# 04__Power_Sheet.net
KiCad netlist of a schematic drawn in Altium Designer
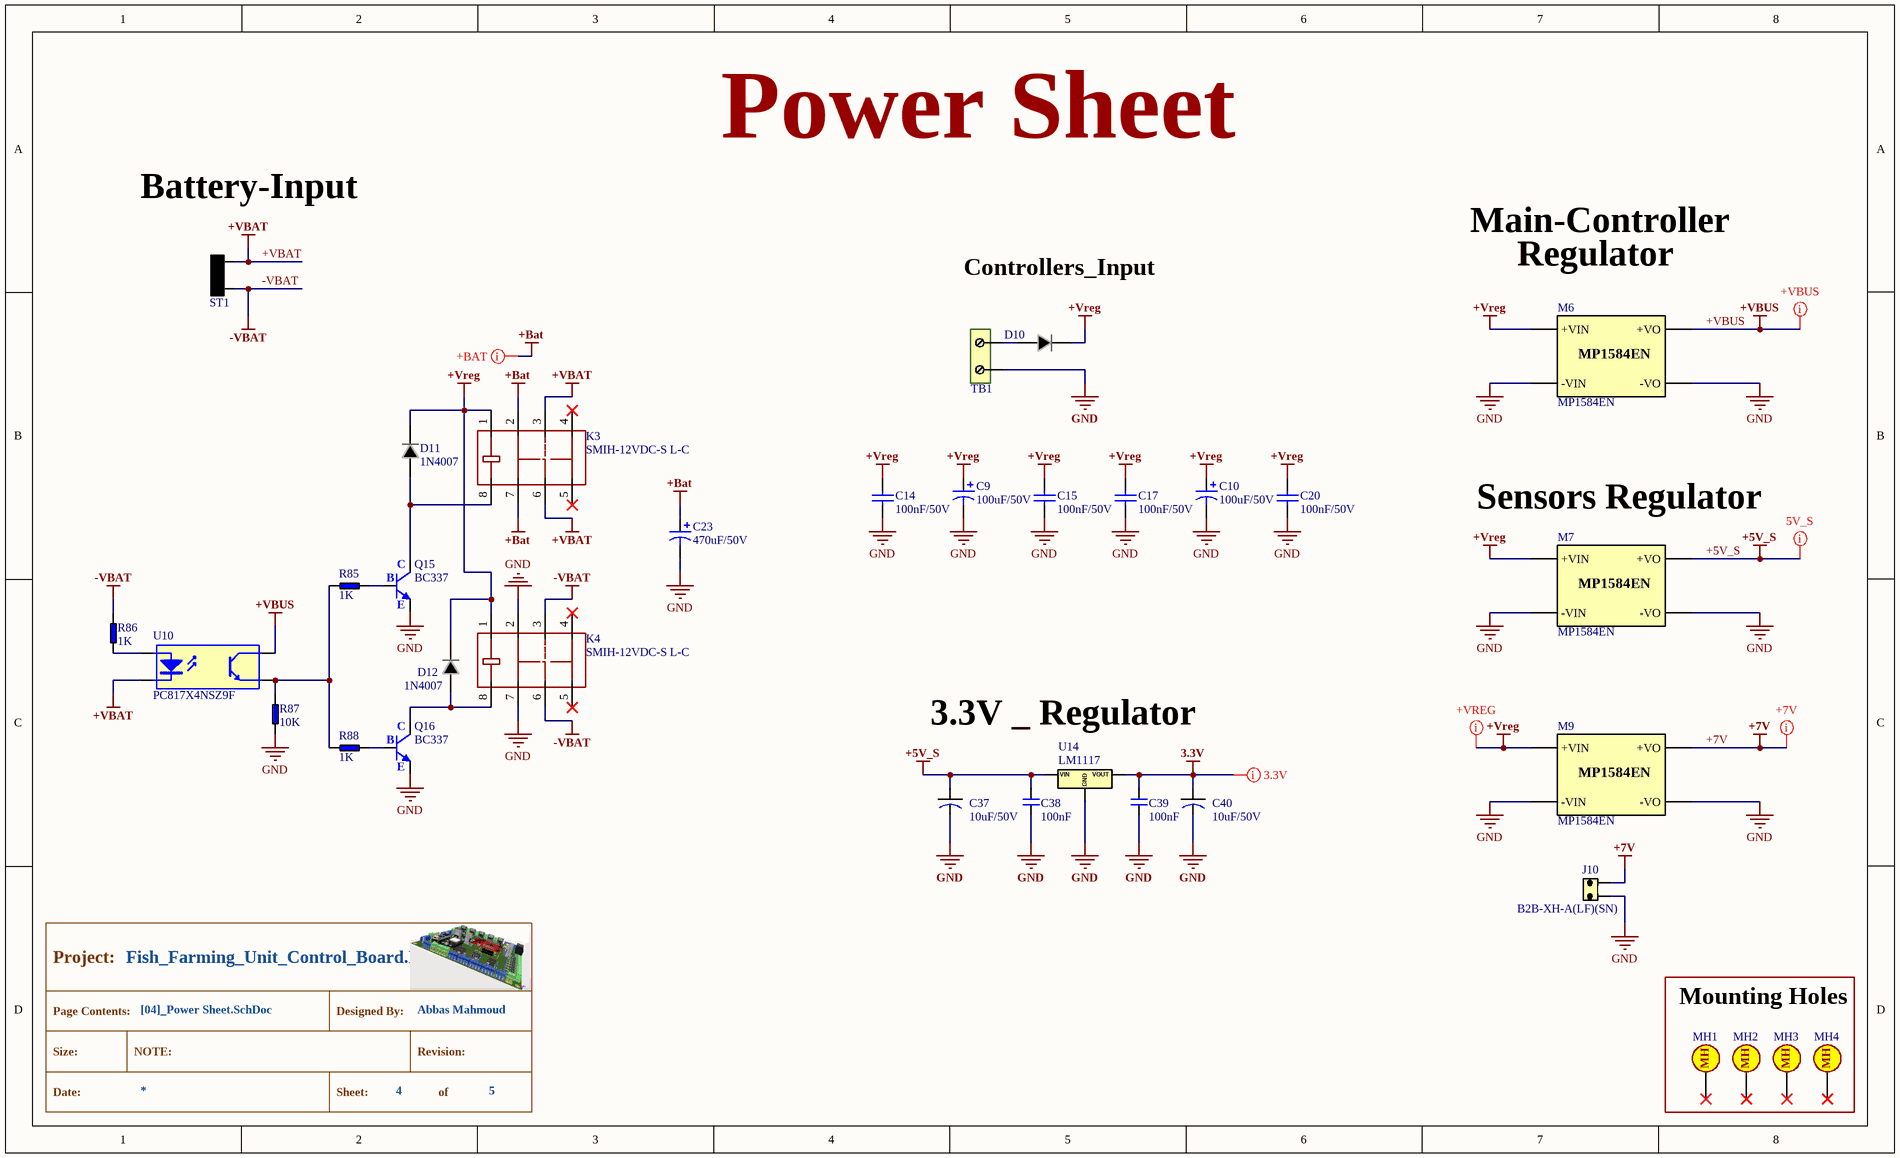
[diagram p0: [04]_Power Sheet.SchDoc]

(export (version "E")
  (design (tool "Eeschema 10.0.6"))
  (components
    (comp (ref "C9")
      (value "100uF/50V")
      (footprint "ECAP - THT - 8X12X3.5MM")
      (description "100uF ±20% 50V 8x12 1000Hrs @ 105℃ Radial,8x12mm Aluminum Electrolytic Capacitors - Leaded RoHS")
      (libsource (lib "Altium_Abbas_V3") (part "ECAP - 100uF - 50V"))
    )
    (comp (ref "C10")
      (value "100uF/50V")
      (footprint "ECAP - THT - 8X12X3.5MM")
      (description "100uF ±20% 50V 8x12 1000Hrs @ 105℃ Radial,8x12mm Aluminum Electrolytic Capacitors - Leaded RoHS")
      (libsource (lib "Altium_Abbas_V3") (part "ECAP - 100uF - 50V"))
    )
    (comp (ref "C14")
      (value "100nF/50V")
      (footprint "CCAP - PACKAGE - THT ,P = 2.54 MM")
      (description "100nF -20%~+80% 50V Through Hole,P=2.54mm Ceramic Disc Capacitors RoHS")
      (libsource (lib "Altium_Abbas_V3") (part "CCAP - 100nF - 50V - THT - P = 2.54"))
    )
    (comp (ref "C15")
      (value "100nF/50V")
      (footprint "CCAP - PACKAGE - THT ,P = 2.54 MM")
      (description "100nF -20%~+80% 50V Through Hole,P=2.54mm Ceramic Disc Capacitors RoHS")
      (libsource (lib "Altium_Abbas_V3") (part "CCAP - 100nF - 50V - THT - P = 2.54"))
    )
    (comp (ref "C17")
      (value "100nF/50V")
      (footprint "CCAP - PACKAGE - THT ,P = 2.54 MM")
      (description "100nF -20%~+80% 50V Through Hole,P=2.54mm Ceramic Disc Capacitors RoHS")
      (libsource (lib "Altium_Abbas_V3") (part "CCAP - 100nF - 50V - THT - P = 2.54"))
    )
    (comp (ref "C20")
      (value "100nF/50V")
      (footprint "CCAP - PACKAGE - THT ,P = 2.54 MM")
      (description "100nF -20%~+80% 50V Through Hole,P=2.54mm Ceramic Disc Capacitors RoHS")
      (libsource (lib "Altium_Abbas_V3") (part "CCAP - 100nF - 50V - THT - P = 2.54"))
    )
    (comp (ref "C23")
      (value "470uF/50V")
      (footprint "ECAP - THT - 10X20X5MM")
      (description "470uF ±20% 50V 10x20 1000Hrs @ 105℃ Radial,10x20mm Aluminum Electrolytic Capacitors - Leaded RoHS")
      (libsource (lib "Altium_Abbas_V3") (part "ECAP - 470uF - 50V"))
    )
    (comp (ref "C37")
      (value "10uF/50V")
      (footprint "ECAP 5X11X2MM")
      (description "10uF ±20% 50V 5x11 1000Hrs @ 105℃ Radial,5x11mm Aluminum Electrolytic Capacitors - Leaded RoHS")
      (libsource (lib "Altium_Abbas") (part "ECAP-10uF-50V"))
    )
    (comp (ref "C38")
      (value "100nF")
      (footprint "CCAP 0.1 N Y")
      (libsource (lib "Altium_Abbas") (part "Ceramic_CAP_100nF"))
    )
    (comp (ref "C39")
      (value "100nF")
      (footprint "CCAP 0.1 N Y")
      (libsource (lib "Altium_Abbas") (part "Ceramic_CAP_100nF"))
    )
    (comp (ref "C40")
      (value "10uF/50V")
      (footprint "ECAP 5X11X2MM")
      (description "10uF ±20% 50V 5x11 1000Hrs @ 105℃ Radial,5x11mm Aluminum Electrolytic Capacitors - Leaded RoHS")
      (libsource (lib "Altium_Abbas") (part "ECAP-10uF-50V"))
    )
    (comp (ref "D10")
      (value "1N4007")
      (footprint "DIODE - THT - 10.16P - PACKAGE - DO-41")
      (description "1kV 1A 1V @ 1A DO-41 Diodes - General Purpose RoHS")
      (libsource (lib "Altium_Abbas_V3") (part "Diode - 1N4007 - THT"))
    )
    (comp (ref "D11")
      (value "1N4007")
      (footprint "DIODE - THT - 7.62P - PACKAGE - DO-41")
      (description "1kV 1A 1V @ 1A DO-41 Diodes - General Purpose RoHS")
      (libsource (lib "Altium_Abbas_V3") (part "Diode - 1N4007 - THT"))
    )
    (comp (ref "D12")
      (value "1N4007")
      (footprint "DIODE - THT - 7.62P - PACKAGE - DO-41")
      (description "1kV 1A 1V @ 1A DO-41 Diodes - General Purpose RoHS")
      (libsource (lib "Altium_Abbas_V3") (part "Diode - 1N4007 - THT"))
    )
    (comp (ref "J10")
      (value "B2B-XH-A(LF)(SN)")
      (footprint "XH - 2P - Vertical - Package - THT - P = 2.54")
      (fields (field (name "MANUFACTURER") "JST Sales America"))
      (libsource (lib "Altium_Abbas_V3") (part "XH - Male Header - 2P - THT - Vertical"))
    )
    (comp (ref "K3")
      (value "SMIH-12VDC-S L-C")
      (footprint "RELAY-TH_SMIH-12VDC-SL-C")
      (description "General Purpose Non Latching 12VDC SPDT 16A Through Hole Relays RoHS")
      (libsource (lib "Altium_Abbas_V3") (part "Relay_12V_16A"))
    )
    (comp (ref "K4")
      (value "SMIH-12VDC-S L-C")
      (footprint "RELAY-TH_SMIH-12VDC-SL-C")
      (description "General Purpose Non Latching 12VDC SPDT 16A Through Hole Relays RoHS")
      (libsource (lib "Altium_Abbas_V3") (part "Relay_12V_16A"))
    )
    (comp (ref "M6")
      (value "MP1584EN")
      (footprint "DC TO D CCONVERTER - MP1584")
      (description "DC-DC 4.5-28V to 0.8-20V Output 3A MP1584EN Step Down Buck Converter")
      (libsource (lib "Altium_Modules") (part "DC TO DC CONVERTER - MP1584EN"))
    )
    (comp (ref "M7")
      (value "MP1584EN")
      (footprint "DC TO D CCONVERTER - MP1584")
      (description "DC-DC 4.5-28V to 0.8-20V Output 3A MP1584EN Step Down Buck Converter")
      (libsource (lib "Altium_Modules") (part "DC TO DC CONVERTER - MP1584EN"))
    )
    (comp (ref "M9")
      (value "MP1584EN")
      (footprint "DC TO D CCONVERTER - MP1584")
      (description "DC-DC 4.5-28V to 0.8-20V Output 3A MP1584EN Step Down Buck Converter")
      (libsource (lib "Altium_Modules") (part "DC TO DC CONVERTER - MP1584EN"))
    )
    (comp (ref "MH1")
      (value "MOUNTING HOLE")
      (footprint "MH-3.2X8mm_Round")
      (description "Mounting Hole")
      (libsource (lib "Altium_Abbas") (part "MH"))
    )
    (comp (ref "MH2")
      (value "MOUNTING HOLE")
      (footprint "MH-3.2X8mm_Round")
      (description "Mounting Hole")
      (libsource (lib "Altium_Abbas") (part "MH"))
    )
    (comp (ref "MH3")
      (value "MOUNTING HOLE")
      (footprint "MH-3.2X8mm_Round")
      (description "Mounting Hole")
      (libsource (lib "Altium_Abbas") (part "MH"))
    )
    (comp (ref "MH4")
      (value "MOUNTING HOLE")
      (footprint "MH-3.2X8mm_Round")
      (description "Mounting Hole")
      (libsource (lib "Altium_Abbas") (part "MH"))
    )
    (comp (ref "Q15")
      (value "BC337")
      (footprint "Transistor - THT - PACKAGE - TO-92 / TO-92-3")
      (description "NPN 800mA 45V 625mW TO-92(TO-92-3) Transistors (NPN/PNP) RoHS")
      (libsource (lib "Altium_Abbas_V3") (part "NPN - BC337"))
    )
    (comp (ref "Q16")
      (value "BC337")
      (footprint "Transistor - THT - PACKAGE - TO-92 / TO-92-3")
      (description "NPN 800mA 45V 625mW TO-92(TO-92-3) Transistors (NPN/PNP) RoHS")
      (libsource (lib "Altium_Abbas_V3") (part "NPN - BC337"))
    )
    (comp (ref "R85")
      (value "1K")
      (footprint "R - THT - P5.0 - 1/4W")
      (description "1K ±1% 1/4W ±100ppm/℃ Axial Metal Film Resistor_ Throuh Hole Technology RoHS")
      (libsource (lib "Altium_Abbas_V3") (part "R1K - THT"))
    )
    (comp (ref "R86")
      (value "1K")
      (footprint "R - THT - P5.0 - 1/4W")
      (description "1K ±1% 1/4W ±100ppm/℃ Axial Metal Film Resistor_ Throuh Hole Technology RoHS")
      (libsource (lib "Altium_Abbas_V3") (part "R1K - THT"))
    )
    (comp (ref "R87")
      (value "10K")
      (footprint "R - THT - P5.0 - 1/4W")
      (description "10K ±1% 1/4W ±100ppm/℃ Axial Metal Film Resistor_ Throuh Hole Technology RoHS")
      (libsource (lib "Altium_Abbas_V3") (part "R10K - THT"))
    )
    (comp (ref "R88")
      (value "1K")
      (footprint "R - THT - P5.0 - 1/4W")
      (description "1K ±1% 1/4W ±100ppm/℃ Axial Metal Film Resistor_ Throuh Hole Technology RoHS")
      (libsource (lib "Altium_Abbas_V3") (part "R1K - THT"))
    )
    (comp (ref "ST1")
      (value "SCREW TERMINAL")
      (footprint "SCREW TERMINAL")
      (description "Barrier Terminal Block 2 Pin with cover 300V/25A")
      (libsource (lib "Altium_Abbas") (part "SCREW TERMINAL"))
    )
    (comp (ref "TB1")
      (value "2 Pins Pluggable")
      (footprint "TERMINAL BLOCK - 2 PINS - PACKAGE - PLUGGABLE - THT - P = 5.08MM - Horizontal _ Plug+Receptable")
      (libsource (lib "Altium_Abbas_V3") (part "Terminal Block - 2 Pins - Pluggable"))
    )
    (comp (ref "U10")
      (value "PC817X4NSZ9F")
      (footprint "ICB - DIP-4")
      (description "Optoisolator Transistor Output 5000Vrms 1 Channel 4-DIP")
      (fields (field (name "MANUFACTURER") "Sharp Microelectronics"))
      (libsource (lib "Altium_Abbas_V3") (part "IC - PC817X4NSZ9F"))
    )
    (comp (ref "U14")
      (value "LM1117")
      (footprint "V-REG/Heatsink - TO - 220")
      (description "IC LM1117-3.3V")
      (libsource (lib "Altium_Abbas") (part "LM117"))
    )
  )
  (nets
    (net (code "1") (name "+5V_S") (class "Default")
      (node (ref "C37") (pin "A") (pintype "passive"))
      (node (ref "C38") (pin "1") (pintype "passive"))
      (node (ref "M7") (pin "+VO") (pinfunction "+VO_+VO") (pintype "power_in"))
      (node (ref "U14") (pin "3") (pinfunction "VIN_3") (pintype "passive"))
    )
    (net (code "2") (name "+7V") (class "Default")
      (node (ref "J10") (pin "2") (pinfunction "2_2") (pintype "passive"))
      (node (ref "M9") (pin "+VO") (pinfunction "+VO_+VO") (pintype "power_in"))
    )
    (net (code "3") (name "+Bat") (class "Default")
      (node (ref "C23") (pin "A") (pinfunction "A_A") (pintype "passive"))
      (node (ref "K3") (pin "2") (pinfunction "2_2") (pintype "passive"))
      (node (ref "K3") (pin "7") (pinfunction "7_7") (pintype "passive"))
    )
    (net (code "4") (name "+VBAT") (class "Default")
      (node (ref "K3") (pin "3") (pinfunction "3_3") (pintype "passive"))
      (node (ref "K3") (pin "6") (pinfunction "6_6") (pintype "passive"))
      (node (ref "ST1") (pin "1") (pinfunction "AC_1") (pintype "passive"))
      (node (ref "U10") (pin "2") (pinfunction "K_2") (pintype "passive"))
    )
    (net (code "5") (name "+VBUS") (class "Default")
      (node (ref "M6") (pin "+VO") (pinfunction "+VO_+VO") (pintype "power_in"))
      (node (ref "U10") (pin "4") (pinfunction "C_4") (pintype "passive"))
    )
    (net (code "6") (name "+Vreg") (class "Default")
      (node (ref "C10") (pin "A") (pinfunction "A_A") (pintype "passive"))
      (node (ref "C14") (pin "1") (pinfunction "1_1") (pintype "passive"))
      (node (ref "C15") (pin "1") (pinfunction "1_1") (pintype "passive"))
      (node (ref "C17") (pin "1") (pinfunction "1_1") (pintype "passive"))
      (node (ref "C20") (pin "1") (pinfunction "1_1") (pintype "passive"))
      (node (ref "C9") (pin "A") (pinfunction "A_A") (pintype "passive"))
      (node (ref "D10") (pin "K") (pinfunction "K_K") (pintype "passive"))
      (node (ref "D11") (pin "K") (pinfunction "K_K") (pintype "passive"))
      (node (ref "D12") (pin "K") (pinfunction "K_K") (pintype "passive"))
      (node (ref "K3") (pin "1") (pinfunction "1_1") (pintype "passive"))
      (node (ref "K4") (pin "1") (pinfunction "1_1") (pintype "passive"))
      (node (ref "M6") (pin "+VIN") (pinfunction "+VIN_+VIN") (pintype "power_in"))
      (node (ref "M7") (pin "+VIN") (pinfunction "+VIN_+VIN") (pintype "power_in"))
      (node (ref "M9") (pin "+VIN") (pinfunction "+VIN_+VIN") (pintype "power_in"))
    )
    (net (code "7") (name "-VBAT") (class "Default")
      (node (ref "K4") (pin "3") (pinfunction "3_3") (pintype "passive"))
      (node (ref "K4") (pin "6") (pinfunction "6_6") (pintype "passive"))
      (node (ref "R86") (pin "2") (pinfunction "6_2") (pintype "passive"))
      (node (ref "ST1") (pin "2") (pinfunction "AC_2") (pintype "passive"))
    )
    (net (code "8") (name "3.3V") (class "Default")
      (node (ref "C39") (pin "1") (pintype "passive"))
      (node (ref "C40") (pin "A") (pintype "passive"))
      (node (ref "U14") (pin "2") (pinfunction "VOUT_2") (pintype "passive"))
    )
    (net (code "9") (name "GND") (class "Default")
      (node (ref "C10") (pin "K") (pinfunction "K_K") (pintype "passive"))
      (node (ref "C14") (pin "2") (pinfunction "2_2") (pintype "passive"))
      (node (ref "C15") (pin "2") (pinfunction "2_2") (pintype "passive"))
      (node (ref "C17") (pin "2") (pinfunction "2_2") (pintype "passive"))
      (node (ref "C20") (pin "2") (pinfunction "2_2") (pintype "passive"))
      (node (ref "C23") (pin "K") (pinfunction "K_K") (pintype "passive"))
      (node (ref "C37") (pin "K") (pintype "passive"))
      (node (ref "C38") (pin "2") (pintype "passive"))
      (node (ref "C39") (pin "2") (pintype "passive"))
      (node (ref "C40") (pin "K") (pintype "passive"))
      (node (ref "C9") (pin "K") (pinfunction "K_K") (pintype "passive"))
      (node (ref "J10") (pin "1") (pinfunction "1_1") (pintype "passive"))
      (node (ref "K4") (pin "2") (pinfunction "2_2") (pintype "passive"))
      (node (ref "K4") (pin "7") (pinfunction "7_7") (pintype "passive"))
      (node (ref "M6") (pin "-VIN") (pinfunction "-VIN_-VIN") (pintype "power_in"))
      (node (ref "M6") (pin "-VO") (pinfunction "-VO_-VO") (pintype "power_in"))
      (node (ref "M7") (pin "-VIN") (pinfunction "-VIN_-VIN") (pintype "power_in"))
      (node (ref "M7") (pin "-VO") (pinfunction "-VO_-VO") (pintype "power_in"))
      (node (ref "M9") (pin "-VIN") (pinfunction "-VIN_-VIN") (pintype "power_in"))
      (node (ref "M9") (pin "-VO") (pinfunction "-VO_-VO") (pintype "power_in"))
      (node (ref "Q15") (pin "1") (pinfunction "E_1") (pintype "passive"))
      (node (ref "Q16") (pin "1") (pinfunction "E_1") (pintype "passive"))
      (node (ref "R87") (pin "1") (pinfunction "5_1") (pintype "passive"))
      (node (ref "TB1") (pin "2") (pinfunction "2_2") (pintype "passive"))
      (node (ref "U14") (pin "1") (pinfunction "GND_1") (pintype "passive"))
    )
    (net (code "10") (name "Net-(D10-PadA)") (class "Default")
      (node (ref "D10") (pin "A") (pinfunction "A_A") (pintype "passive"))
      (node (ref "TB1") (pin "1") (pinfunction "1_1") (pintype "passive"))
    )
    (net (code "11") (name "Net-(Q15-B)") (class "Default")
      (node (ref "Q15") (pin "2") (pinfunction "B_2") (pintype "passive"))
      (node (ref "R85") (pin "2") (pinfunction "6_2") (pintype "passive"))
    )
    (net (code "12") (name "Net-(Q15-C)") (class "Default")
      (node (ref "D11") (pin "A") (pinfunction "A_A") (pintype "passive"))
      (node (ref "K3") (pin "8") (pinfunction "8_8") (pintype "passive"))
      (node (ref "Q15") (pin "3") (pinfunction "C_3") (pintype "passive"))
    )
    (net (code "13") (name "Net-(Q16-B)") (class "Default")
      (node (ref "Q16") (pin "2") (pinfunction "B_2") (pintype "passive"))
      (node (ref "R88") (pin "2") (pinfunction "6_2") (pintype "passive"))
    )
    (net (code "14") (name "Net-(Q16-C)") (class "Default")
      (node (ref "D12") (pin "A") (pinfunction "A_A") (pintype "passive"))
      (node (ref "K4") (pin "8") (pinfunction "8_8") (pintype "passive"))
      (node (ref "Q16") (pin "3") (pinfunction "C_3") (pintype "passive"))
    )
    (net (code "15") (name "Net-(R85-5)") (class "Default")
      (node (ref "R85") (pin "1") (pinfunction "5_1") (pintype "passive"))
      (node (ref "R87") (pin "2") (pinfunction "6_2") (pintype "passive"))
      (node (ref "R88") (pin "1") (pinfunction "5_1") (pintype "passive"))
      (node (ref "U10") (pin "3") (pinfunction "E_3") (pintype "passive"))
    )
    (net (code "16") (name "Net-(R86-5)") (class "Default")
      (node (ref "R86") (pin "1") (pinfunction "5_1") (pintype "passive"))
      (node (ref "U10") (pin "1") (pinfunction "A_1") (pintype "passive"))
    )
    (net (code "17") (name "unconnected-(K3-Pad4)") (class "Default")
      (node (ref "K3") (pin "4") (pinfunction "4_4") (pintype "passive+no_connect"))
    )
    (net (code "18") (name "unconnected-(K3-Pad5)") (class "Default")
      (node (ref "K3") (pin "5") (pinfunction "5_5") (pintype "passive+no_connect"))
    )
    (net (code "19") (name "unconnected-(K4-Pad4)") (class "Default")
      (node (ref "K4") (pin "4") (pinfunction "4_4") (pintype "passive+no_connect"))
    )
    (net (code "20") (name "unconnected-(K4-Pad5)") (class "Default")
      (node (ref "K4") (pin "5") (pinfunction "5_5") (pintype "passive+no_connect"))
    )
    (net (code "21") (name "unconnected-(MH1-PadMH)") (class "Default")
      (node (ref "MH1") (pin "MH") (pinfunction "MH_MH") (pintype "passive+no_connect"))
    )
    (net (code "22") (name "unconnected-(MH2-PadMH)") (class "Default")
      (node (ref "MH2") (pin "MH") (pinfunction "MH_MH") (pintype "passive+no_connect"))
    )
    (net (code "23") (name "unconnected-(MH3-PadMH)") (class "Default")
      (node (ref "MH3") (pin "MH") (pinfunction "MH_MH") (pintype "passive+no_connect"))
    )
    (net (code "24") (name "unconnected-(MH4-PadMH)") (class "Default")
      (node (ref "MH4") (pin "MH") (pinfunction "MH_MH") (pintype "passive+no_connect"))
    )
  )
)
